# CurrentRestrictionBoard_V1_0.net
KiCad netlist of a schematic drawn in EAGLE
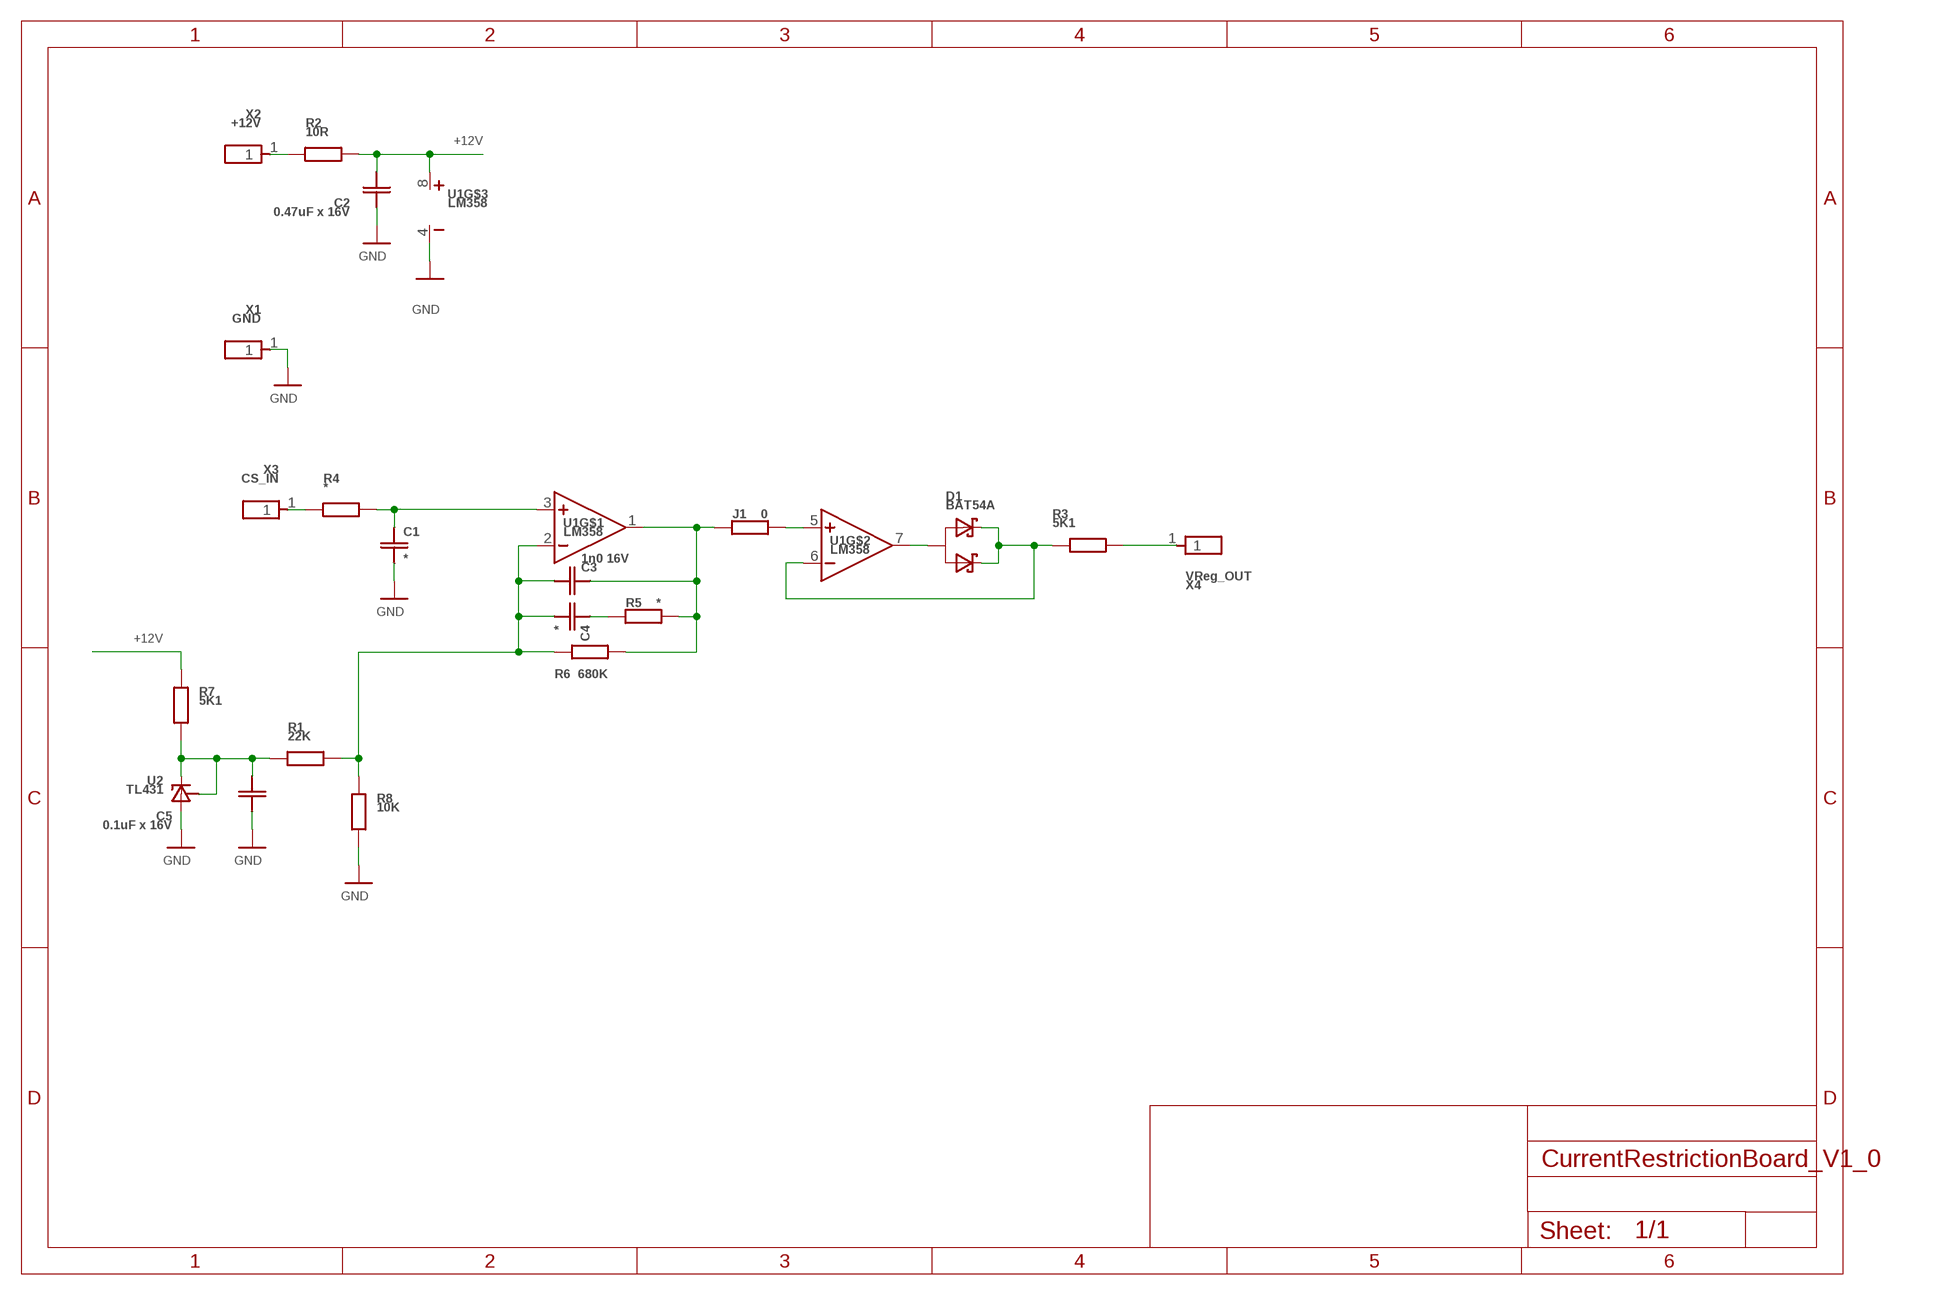
[diagram p0: schematic, sheet 1]

(export (version "E")
  (design (tool "Eeschema 10.0.6"))
  (components
    (comp (ref "C1")
      (value "*")
      (footprint "eagle-import:RSMD_0603")
      (libsource (lib "eagle-import") (part "CSMD_0603"))
    )
    (comp (ref "C2")
      (value "0.47uF x 16V")
      (footprint "eagle-import:RSMD_0805")
      (libsource (lib "eagle-import") (part "CSMD_0805"))
    )
    (comp (ref "C3")
      (value "1n0 16V")
      (footprint "eagle-import:RSMD_0603")
      (libsource (lib "eagle-import") (part "CSMD_0603"))
    )
    (comp (ref "C4")
      (value "*")
      (footprint "eagle-import:RSMD_0603")
      (libsource (lib "eagle-import") (part "CSMD_0603"))
    )
    (comp (ref "C5")
      (value "0.1uF x 16V")
      (footprint "eagle-import:RSMD_0603")
      (libsource (lib "eagle-import") (part "CSMD_0603"))
    )
    (comp (ref "D1")
      (value "BAT54A")
      (footprint "eagle-import:SOT23_SMALL_PADS")
      (libsource (lib "eagle-import") (part "BAT54ASOT23_SMALL_PADS"))
    )
    (comp (ref "J1")
      (value "0")
      (footprint "eagle-import:RSMD_0805")
      (libsource (lib "eagle-import") (part "RSMD_0805"))
    )
    (comp (ref "R1")
      (value "22K")
      (footprint "eagle-import:RSMD_0603")
      (libsource (lib "eagle-import") (part "RSMD_0603"))
    )
    (comp (ref "R2")
      (value "10R")
      (footprint "eagle-import:RSMD_0805")
      (libsource (lib "eagle-import") (part "RSMD_0805"))
    )
    (comp (ref "R3")
      (value "5K1")
      (footprint "eagle-import:RSMD_0603")
      (libsource (lib "eagle-import") (part "RSMD_0603"))
    )
    (comp (ref "R4")
      (value "*")
      (footprint "eagle-import:RSMD_0603")
      (libsource (lib "eagle-import") (part "RSMD_0603"))
    )
    (comp (ref "R5")
      (value "*")
      (footprint "eagle-import:RSMD_0603")
      (libsource (lib "eagle-import") (part "RSMD_0603"))
    )
    (comp (ref "R6")
      (value "680K")
      (footprint "eagle-import:RSMD_0603")
      (libsource (lib "eagle-import") (part "RSMD_0603"))
    )
    (comp (ref "R7")
      (value "5K1")
      (footprint "eagle-import:RSMD_0805")
      (libsource (lib "eagle-import") (part "RSMD_0805"))
    )
    (comp (ref "R8")
      (value "10K")
      (footprint "eagle-import:RSMD_0603")
      (libsource (lib "eagle-import") (part "RSMD_0603"))
    )
    (comp (ref "U1")
      (value "LM358")
      (footprint "eagle-import:SOIC8")
      (libsource (lib "eagle-import") (part "LM358SOIC8"))
    )
    (comp (ref "U2")
      (value "TL431")
      (footprint "eagle-import:SOT23")
      (libsource (lib "eagle-import") (part "TL431SOT23"))
    )
    (comp (ref "X1")
      (value "GND")
      (footprint "eagle-import:PIN1X1_2.5X2.5MM")
      (libsource (lib "eagle-import") (part "PIN1X1PAD_2.5X2.5"))
    )
    (comp (ref "X2")
      (value "+12V")
      (footprint "eagle-import:PIN1X1_2.5X2.5MM")
      (libsource (lib "eagle-import") (part "PIN1X1PAD_2.5X2.5"))
    )
    (comp (ref "X3")
      (value "CS_IN")
      (footprint "eagle-import:PIN1X1_2.5X2.5MM")
      (libsource (lib "eagle-import") (part "PIN1X1PAD_2.5X2.5"))
    )
    (comp (ref "X4")
      (value "VReg_OUT")
      (footprint "eagle-import:PIN1X1_2.5X2.5MM")
      (libsource (lib "eagle-import") (part "PIN1X1PAD_2.5X2.5"))
    )
  )
  (nets
    (net (code "1") (name "/+12V") (class "Default")
      (node (ref "C2") (pin "PAD_1") (pinfunction "PIN1_PAD_1") (pintype "bidirectional"))
      (node (ref "R2") (pin "PAD_0") (pinfunction "PIN0_PAD_0") (pintype "passive"))
      (node (ref "R7") (pin "PAD_1") (pinfunction "PIN1_PAD_1") (pintype "passive"))
      (node (ref "U1") (pin "8") (pinfunction "VCC_8") (pintype "power_in"))
    )
    (net (code "2") (name "GND") (class "Default")
      (node (ref "C1") (pin "PAD_0") (pinfunction "PIN0_PAD_0") (pintype "bidirectional"))
      (node (ref "C2") (pin "PAD_0") (pinfunction "PIN0_PAD_0") (pintype "bidirectional"))
      (node (ref "C5") (pin "PAD_0") (pinfunction "PIN0_PAD_0") (pintype "bidirectional"))
      (node (ref "R8") (pin "PAD_0") (pinfunction "PIN0_PAD_0") (pintype "passive"))
      (node (ref "U1") (pin "4") (pinfunction "GND_4") (pintype "power_in"))
      (node (ref "U2") (pin "3") (pinfunction "ANODE_3") (pintype "passive"))
      (node (ref "X1") (pin "1") (pinfunction "1_1") (pintype "bidirectional"))
    )
    (net (code "3") (name "Net-(C1-PIN1)") (class "Default")
      (node (ref "C1") (pin "PAD_1") (pinfunction "PIN1_PAD_1") (pintype "bidirectional"))
      (node (ref "R4") (pin "PAD_0") (pinfunction "PIN0_PAD_0") (pintype "passive"))
      (node (ref "U1") (pin "3") (pinfunction "IN+_3") (pintype "input"))
    )
    (net (code "4") (name "Net-(C3-PIN0)") (class "Default")
      (node (ref "C3") (pin "PAD_0") (pinfunction "PIN0_PAD_0") (pintype "bidirectional"))
      (node (ref "C4") (pin "PAD_0") (pinfunction "PIN0_PAD_0") (pintype "bidirectional"))
      (node (ref "R1") (pin "PAD_0") (pinfunction "PIN0_PAD_0") (pintype "passive"))
      (node (ref "R6") (pin "PAD_1") (pinfunction "PIN1_PAD_1") (pintype "passive"))
      (node (ref "R8") (pin "PAD_1") (pinfunction "PIN1_PAD_1") (pintype "passive"))
      (node (ref "U1") (pin "2") (pinfunction "IN-_2") (pintype "input"))
    )
    (net (code "5") (name "Net-(C3-PIN1)") (class "Default")
      (node (ref "C3") (pin "PAD_1") (pinfunction "PIN1_PAD_1") (pintype "bidirectional"))
      (node (ref "J1") (pin "PAD_1") (pinfunction "PIN1_PAD_1") (pintype "passive"))
      (node (ref "R5") (pin "PAD_0") (pinfunction "PIN0_PAD_0") (pintype "passive"))
      (node (ref "R6") (pin "PAD_0") (pinfunction "PIN0_PAD_0") (pintype "passive"))
      (node (ref "U1") (pin "1") (pinfunction "OUT_1") (pintype "output"))
    )
    (net (code "6") (name "Net-(C4-PIN1)") (class "Default")
      (node (ref "C4") (pin "PAD_1") (pinfunction "PIN1_PAD_1") (pintype "bidirectional"))
      (node (ref "R5") (pin "PAD_1") (pinfunction "PIN1_PAD_1") (pintype "passive"))
    )
    (net (code "7") (name "Net-(C5-PIN1)") (class "Default")
      (node (ref "C5") (pin "PAD_1") (pinfunction "PIN1_PAD_1") (pintype "bidirectional"))
      (node (ref "R1") (pin "PAD_1") (pinfunction "PIN1_PAD_1") (pintype "passive"))
      (node (ref "R7") (pin "PAD_0") (pinfunction "PIN0_PAD_0") (pintype "passive"))
      (node (ref "U2") (pin "1") (pinfunction "CATHODE_1") (pintype "passive"))
      (node (ref "U2") (pin "2") (pinfunction "REFERENCE_2") (pintype "passive"))
    )
    (net (code "8") (name "Net-(D1-ANODE)") (class "Default")
      (node (ref "D1") (pin "3") (pinfunction "ANODE_3") (pintype "passive"))
      (node (ref "U1") (pin "7") (pinfunction "OUT_7") (pintype "output"))
    )
    (net (code "9") (name "Net-(D1-CATHODE1)") (class "Default")
      (node (ref "D1") (pin "1") (pinfunction "CATHODE1_1") (pintype "passive"))
      (node (ref "D1") (pin "2") (pinfunction "CATHODE2_2") (pintype "passive"))
      (node (ref "R3") (pin "PAD_1") (pinfunction "PIN1_PAD_1") (pintype "passive"))
      (node (ref "U1") (pin "6") (pinfunction "IN-_6") (pintype "input"))
    )
    (net (code "10") (name "Net-(J1-PIN0)") (class "Default")
      (node (ref "J1") (pin "PAD_0") (pinfunction "PIN0_PAD_0") (pintype "passive"))
      (node (ref "U1") (pin "5") (pinfunction "IN+_5") (pintype "input"))
    )
    (net (code "11") (name "Net-(R2-PIN1)") (class "Default")
      (node (ref "R2") (pin "PAD_1") (pinfunction "PIN1_PAD_1") (pintype "passive"))
      (node (ref "X2") (pin "1") (pinfunction "1_1") (pintype "bidirectional"))
    )
    (net (code "12") (name "Net-(R3-PIN0)") (class "Default")
      (node (ref "R3") (pin "PAD_0") (pinfunction "PIN0_PAD_0") (pintype "passive"))
      (node (ref "X4") (pin "1") (pinfunction "1_1") (pintype "bidirectional"))
    )
    (net (code "13") (name "Net-(R4-PIN1)") (class "Default")
      (node (ref "R4") (pin "PAD_1") (pinfunction "PIN1_PAD_1") (pintype "passive"))
      (node (ref "X3") (pin "1") (pinfunction "1_1") (pintype "bidirectional"))
    )
  )
)
